# CANConnector.net
KiCad netlist of a schematic drawn in Altium Designer
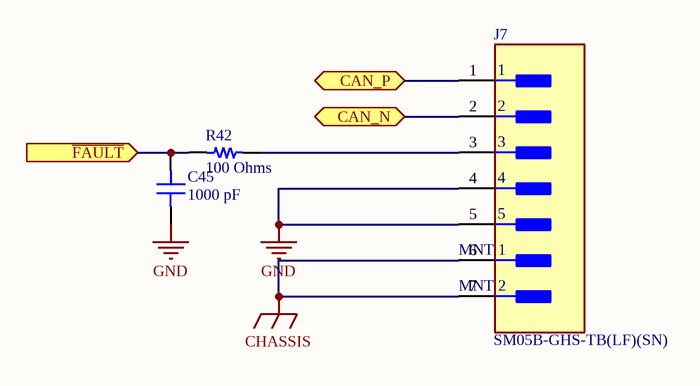
[diagram p0: CANConnector.SchDoc]

(export (version "E")
  (design (tool "Eeschema 10.0.6"))
  (components
    (comp (ref "C45")
      (value "1000 pF")
      (footprint "CAP 0402_1005")
      (description "CAP CER 1000PF 50V C0G/NP0 0402")
      (fields
        (field (name "PART NUMBER") "UMK105CG102JVHF")
        (field (name "CAPACITANCE") "1000 pF")
        (field (name "MANUFACTURER") "Taiyo Yuden")
      )
      (libsource (lib "Celestial Altium Library - altium_library") (part "Capacitor"))
    )
    (comp (ref "J7")
      (value "SM05B-GHS-TB(LF)(SN)")
      (footprint "FP-SM05B-GHS-TB_LF_SN-MFG")
      (description "CONN HEADER SMD R/A 5POS 1.25MM")
      (libsource (lib "Altium Content Vault") (part "8ab9848ea90b119fa28a5ddc5abf419"))
    )
    (comp (ref "R42")
      (value "100 Ohms")
      (footprint "RES 0402_1005")
      (description "RES 100 OHM 1% 1/16W 0402")
      (fields
        (field (name "PART NUMBER") "WR04X1000FTL")
        (field (name "MANUFACTURER") "Walsin Technology Corporation")
      )
      (libsource (lib "Celestial Altium Library - altium_library") (part "Resistor"))
    )
  )
  (nets
    (net (code "1") (name "/CAN_N") (class "Default")
      (node (ref "J7") (pin "2") (pinfunction "2_2") (pintype "passive"))
    )
    (net (code "2") (name "/CAN_P") (class "Default")
      (node (ref "J7") (pin "1") (pinfunction "1_1") (pintype "passive"))
    )
    (net (code "3") (name "/~{FAULT}") (class "Default")
      (node (ref "C45") (pin "2") (pinfunction "2_2") (pintype "passive"))
      (node (ref "R42") (pin "1") (pinfunction "1_1") (pintype "passive"))
    )
    (net (code "4") (name "CHASSIS") (class "Default")
      (node (ref "J7") (pin "6") (pinfunction "MNT_1_6") (pintype "passive"))
      (node (ref "J7") (pin "7") (pinfunction "MNT_2_7") (pintype "passive"))
    )
    (net (code "5") (name "GND") (class "Default")
      (node (ref "C45") (pin "1") (pinfunction "1_1") (pintype "passive"))
      (node (ref "J7") (pin "4") (pinfunction "4_4") (pintype "passive"))
      (node (ref "J7") (pin "5") (pinfunction "5_5") (pintype "passive"))
    )
    (net (code "6") (name "Net-(J7-Pad3)") (class "Default")
      (node (ref "J7") (pin "3") (pinfunction "3_3") (pintype "passive"))
      (node (ref "R42") (pin "2") (pinfunction "2_2") (pintype "passive"))
    )
  )
)
